# top.net
KiCad netlist of a schematic drawn in Altium Designer
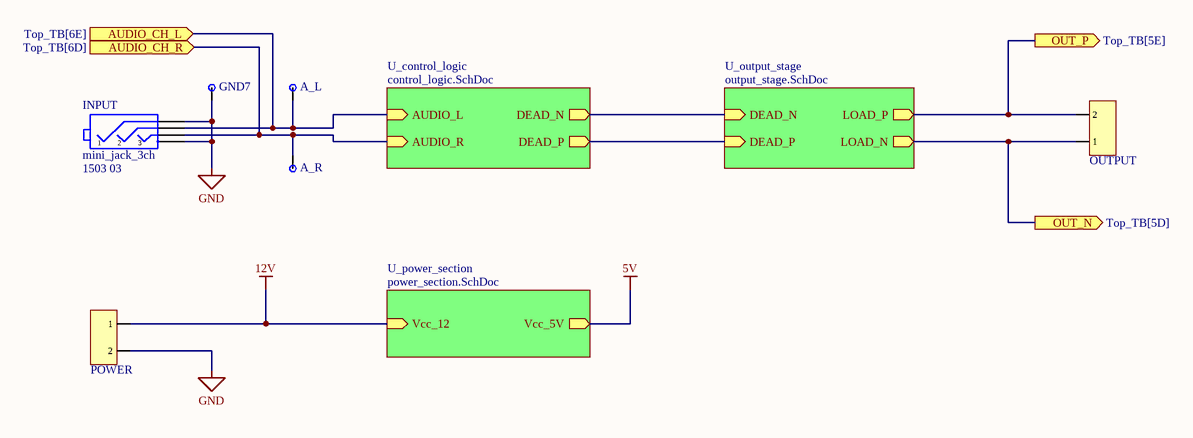
[diagram p0: top.SchDoc]

(export (version "E")
  (design (tool "Eeschema 10.0.6"))
  (components
    (comp (ref "A_L")
      (value "TestPoint")
      (footprint "TestPoint_SMT")
      (description "Test Point")
      (libsource (lib "INT_lib") (part "TestPoint"))
    )
    (comp (ref "A_R")
      (value "TestPoint")
      (footprint "TestPoint_SMT")
      (description "Test Point")
      (libsource (lib "INT_lib") (part "TestPoint"))
    )
    (comp (ref "GND7")
      (value "TestPoint")
      (footprint "TestPoint_SMT")
      (description "Test Point")
      (libsource (lib "INT_lib") (part "TestPoint"))
    )
    (comp (ref "INPUT")
      (value "mini_jack_3ch")
      (footprint "150303_mini_jack3.5mm")
      (description "Connector: Jack 3.5mm; socket; female; stereo; tracks: 3")
      (fields (field (name "PART NUMBER") "1503 03"))
      (libsource (lib "INT_lib") (part "mini_jack_3ch"))
    )
    (comp (ref "OUTPUT")
      (value "Connector_1x2")
      (footprint "TerminalBlock_1x2")
      (description "Fixed Terminal Blocks Terminal block, screw type, 1x2")
      (libsource (lib "") (part "Connector_1x2_1"))
    )
    (comp (ref "POWER")
      (value "Connector_1x2")
      (footprint "TerminalBlock_1x2")
      (description "Fixed Terminal Blocks Terminal block, screw type, 1x2")
      (libsource (lib "INT_lib") (part "Connector_1x2"))
    )
  )
  (nets
    (net (code "1") (name "/AUDIO_CH_L") (class "Default")
      (node (ref "A_L") (pin "1") (pinfunction "1_1") (pintype "passive"))
      (node (ref "INPUT") (pin "2") (pinfunction "2_2") (pintype "passive"))
    )
    (net (code "2") (name "/AUDIO_CH_R") (class "Default")
      (node (ref "A_R") (pin "1") (pinfunction "1_1") (pintype "passive"))
      (node (ref "INPUT") (pin "3") (pinfunction "3_3") (pintype "passive"))
    )
    (net (code "5") (name "/OUT_N") (class "Default")
      (node (ref "OUTPUT") (pin "1") (pinfunction "1_1") (pintype "passive"))
    )
    (net (code "6") (name "/OUT_P") (class "Default")
      (node (ref "OUTPUT") (pin "2") (pinfunction "2_2") (pintype "passive"))
    )
    (net (code "8") (name "12V") (class "Default")
      (node (ref "POWER") (pin "1") (pinfunction "1_1") (pintype "passive"))
    )
    (net (code "9") (name "GND") (class "Default")
      (node (ref "GND7") (pin "1") (pinfunction "1_1") (pintype "passive"))
      (node (ref "INPUT") (pin "1") (pinfunction "1_1") (pintype "passive"))
      (node (ref "INPUT") (pin "4") (pinfunction "4_4") (pintype "passive"))
      (node (ref "POWER") (pin "2") (pinfunction "2_2") (pintype "passive"))
    )
  )
)
